# Shield_Amir_Shalev_V_0_1.net
KiCad netlist of a schematic drawn in EasyEDA
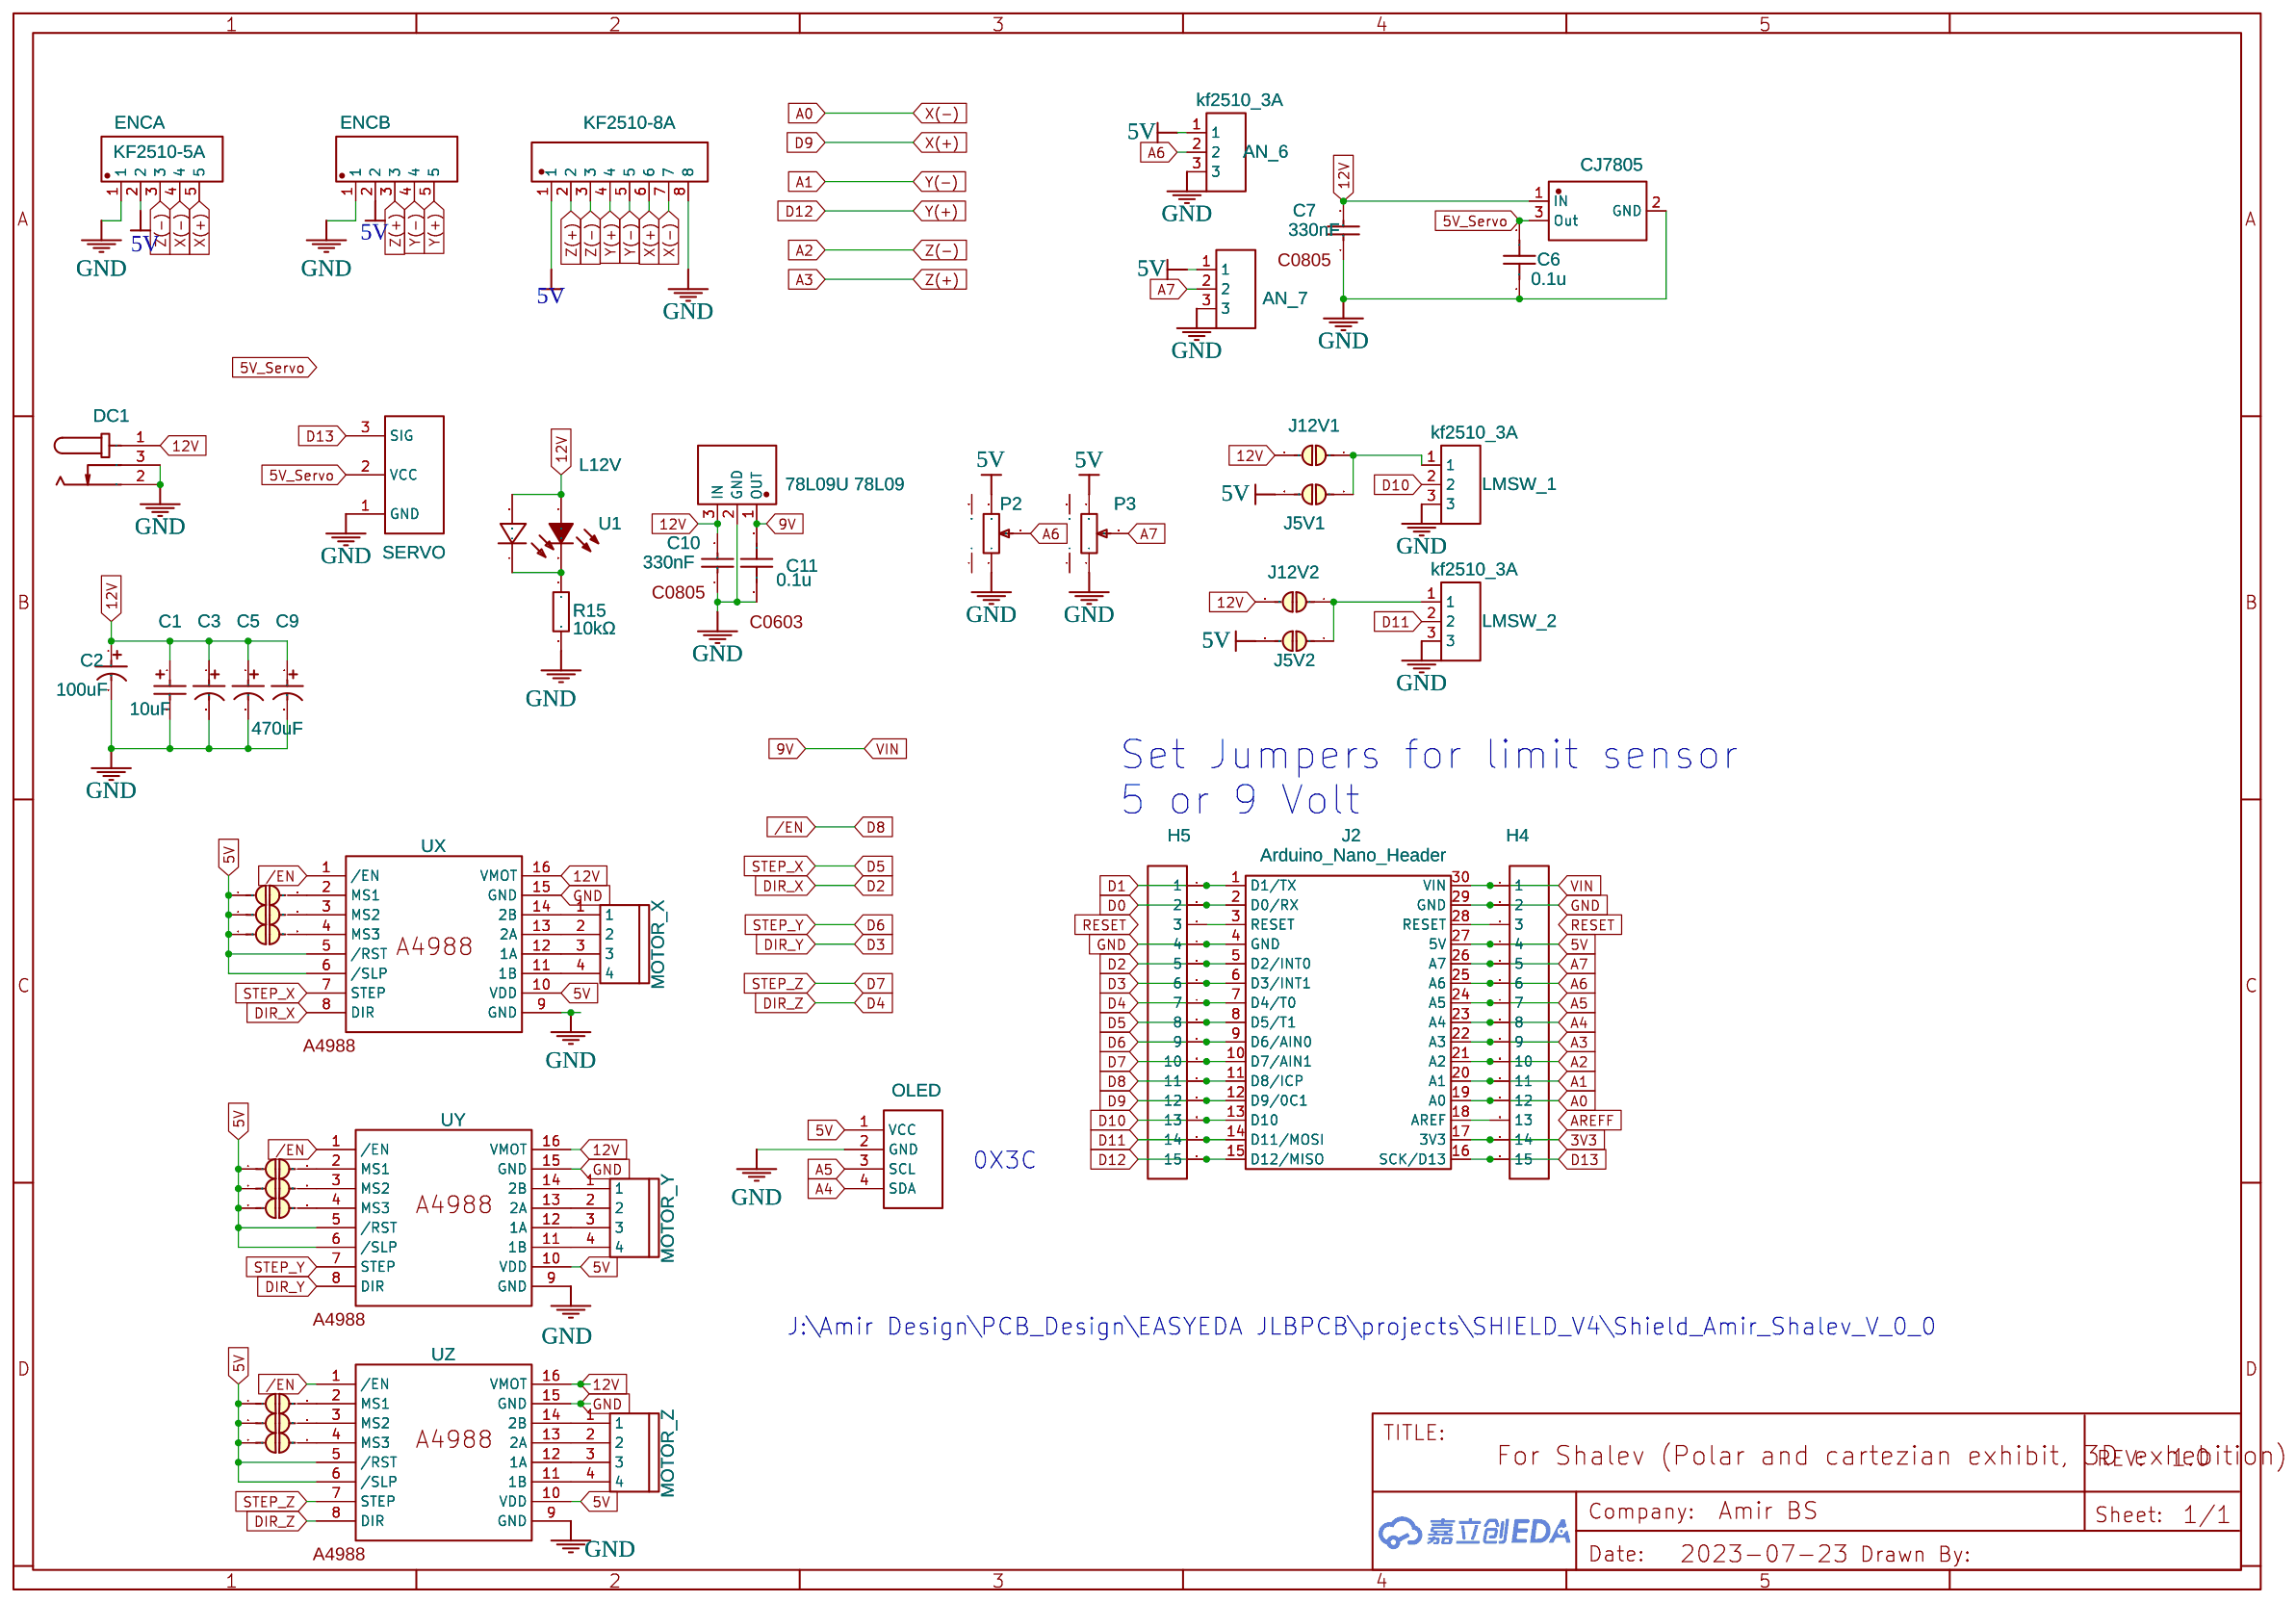
[diagram p0: schematic sheet]

(export (version "E")
  (design (tool "Eeschema 10.0.6"))
  (components
    (comp (ref "AN_6")
      (value "kf2510_3A")
      (fields (field (name "Manufacturer Part") "2510-3A") (field (name "Manufacturer") "BOOMELE(博穆精密)"))
      (libsource (lib "") (part "kf2510_3A_1"))
    )
    (comp (ref "AN_7")
      (value "kf2510_3A")
      (fields (field (name "Manufacturer Part") "2510-3A") (field (name "Manufacturer") "BOOMELE(博穆精密)"))
      (libsource (lib "") (part "kf2510_3A_1"))
    )
    (comp (ref "C1")
      (value "10uF")
      (fields (field (name "Manufacturer Part") "TAJA106K016RNJ") (field (name "Manufacturer") "Kyocera AVX"))
      (libsource (lib "") (part "TAJA106K016RNJ"))
    )
    (comp (ref "C2")
      (value "100uF")
      (fields
        (field (name "Manufacturer Part") "KM107M035E11RR0VH2FP0")
        (field (name "Manufacturer") "CX(承兴)")
      )
      (libsource (lib "") (part "100uF 35V 6.3*11"))
    )
    (comp (ref "C3")
      (value "470uF")
      (fields
        (field (name "Manufacturer Part") "GR477M025F12RR0VH4FP0")
        (field (name "Manufacturer") "CX(承兴)")
      )
      (libsource (lib "") (part "470uF 25V 8*12Black high frequency"))
    )
    (comp (ref "C5")
      (value "470uF")
      (fields
        (field (name "Manufacturer Part") "GR477M025F12RR0VH4FP0")
        (field (name "Manufacturer") "CX(承兴)")
      )
      (libsource (lib "") (part "470uF 25V 8*12Black high frequency"))
    )
    (comp (ref "C6") (value "0.1u") (libsource (lib "") (part "C_0603_US_1")))
    (comp (ref "C7")
      (value "330nF")
      (fields (field (name "Manufacturer Part") "0805B334K500NT") (field (name "Manufacturer") "FH(风华)"))
      (libsource (lib "") (part "0805B334K500NT"))
    )
    (comp (ref "C9")
      (value "470uF")
      (fields
        (field (name "Manufacturer Part") "GR477M025F12RR0VH4FP0")
        (field (name "Manufacturer") "CX(承兴)")
      )
      (libsource (lib "") (part "470uF 25V 8*12Black high frequency"))
    )
    (comp (ref "C10")
      (value "330nF")
      (fields (field (name "Manufacturer Part") "0805B334K500NT") (field (name "Manufacturer") "FH(风华)"))
      (libsource (lib "") (part "0805B334K500NT"))
    )
    (comp (ref "C11") (value "0.1u") (libsource (lib "") (part "C_0603_US")))
    (comp (ref "CN2")
      (value "KF2510-8A")
      (fields (field (name "Manufacturer Part") "2510-8A") (field (name "Manufacturer") "BOOMELE(博穆精密)"))
      (libsource (lib "") (part "KF2510-8A"))
    )
    (comp (ref "DC1")
      (value "DC")
      (fields
        (field (name "BOM_Manufacturer Part") "DC005-2.0MM")
        (field (name "BOM_Supplier Part") "C111567")
      )
      (libsource (lib "") (part "DC005-2.0MM"))
    )
    (comp (ref "ENCA")
      (value "KF2510-5A")
      (fields (field (name "Manufacturer Part") "2510-5A") (field (name "Manufacturer") "BOOMELE(博穆精密)"))
      (libsource (lib "") (part "KF2510-5A_1"))
    )
    (comp (ref "ENCB")
      (value "KF2510-5A")
      (fields (field (name "Manufacturer Part") "2510-5A") (field (name "Manufacturer") "BOOMELE(博穆精密)"))
      (libsource (lib "") (part "KF2510-5A"))
    )
    (comp (ref "H4")
      (value "HDR-F-2.54_1x15")
      (fields (field (name "BOM_Supplier Part") "C124408"))
      (libsource (lib "") (part "HDR-F-2.54_1x15"))
    )
    (comp (ref "H5")
      (value "HDR-F-2.54_1x15")
      (fields (field (name "BOM_Supplier Part") "C124408"))
      (libsource (lib "") (part "HDR-F-2.54_1x15_1"))
    )
    (comp (ref "J2") (value "Arduino_Nano_Header") (libsource (lib "") (part "Arduino_Nano_Header")))
    (comp (ref "J5V1") (value "JUMPER-SMT_2") (libsource (lib "") (part "JUMPER-SMT_2_3")))
    (comp (ref "J5V2") (value "JUMPER-SMT_2") (libsource (lib "") (part "JUMPER-SMT_2_3")))
    (comp (ref "J12V1") (value "JUMPER-SMT_2") (libsource (lib "") (part "JUMPER-SMT_2_4")))
    (comp (ref "J12V2") (value "JUMPER-SMT_2") (libsource (lib "") (part "JUMPER-SMT_2_4")))
    (comp (ref "JX1") (value "JUMPER-SMT_2") (libsource (lib "") (part "JUMPER-SMT_2_1")))
    (comp (ref "JX2") (value "JUMPER-SMT_2") (libsource (lib "") (part "JUMPER-SMT_2_1")))
    (comp (ref "JX3") (value "JUMPER-SMT_2") (libsource (lib "") (part "JUMPER-SMT_2_1")))
    (comp (ref "JY1") (value "JUMPER-SMT_2") (libsource (lib "") (part "JUMPER-SMT_2_2")))
    (comp (ref "JY2") (value "JUMPER-SMT_2") (libsource (lib "") (part "JUMPER-SMT_2_2")))
    (comp (ref "JY3") (value "JUMPER-SMT_2") (libsource (lib "") (part "JUMPER-SMT_2_2")))
    (comp (ref "JZ1") (value "JUMPER-SMT_2") (libsource (lib "") (part "JUMPER-SMT_2")))
    (comp (ref "JZ2") (value "JUMPER-SMT_2") (libsource (lib "") (part "JUMPER-SMT_2")))
    (comp (ref "JZ3") (value "JUMPER-SMT_2") (libsource (lib "") (part "JUMPER-SMT_2")))
    (comp (ref "L12V")
      (value "LED")
      (fields
        (field (name "BOM_Manufacturer Part") "19-217/BHC-ZL1M2RY/3T")
        (field (name "BOM_Supplier Part") "C72041")
      )
      (libsource (lib "") (part "19-217/BHC-ZL1M2RY/3T"))
    )
    (comp (ref "LMSW_1")
      (value "kf2510_3A")
      (fields (field (name "Manufacturer Part") "2510-3A") (field (name "Manufacturer") "BOOMELE(博穆精密)"))
      (libsource (lib "") (part "kf2510_3A"))
    )
    (comp (ref "LMSW_2")
      (value "kf2510_3A")
      (fields (field (name "Manufacturer Part") "2510-3A") (field (name "Manufacturer") "BOOMELE(博穆精密)"))
      (libsource (lib "") (part "kf2510_3A"))
    )
    (comp (ref "MOTOR_X")
      (value "XH2.54-4AW")
      (fields (field (name "Manufacturer Part") "XH-4AW") (field (name "Manufacturer") "BOOMELE(博穆精密)"))
      (libsource (lib "") (part "XH2.54-4AW_1"))
    )
    (comp (ref "MOTOR_Y")
      (value "XH2.54-4AW")
      (fields (field (name "Manufacturer Part") "XH-4AW") (field (name "Manufacturer") "BOOMELE(博穆精密)"))
      (libsource (lib "") (part "XH2.54-4AW"))
    )
    (comp (ref "MOTOR_Z")
      (value "XH2.54-4AW")
      (fields (field (name "Manufacturer Part") "XH-4AW") (field (name "Manufacturer") "BOOMELE(博穆精密)"))
      (libsource (lib "") (part "XH2.54-4AW_2"))
    )
    (comp (ref "OLED")
      (value "1.3 inch OLED SSH1106 I2C 128x64 copy")
      (libsource (lib "") (part "1.3 inch OLED SSH1106 I2C 128x64 copy"))
    )
    (comp (ref "P2")
      (value "长柄旋转电位器")
      (fields (field (name "BOM_Supplier Part") "C2874842"))
      (libsource (lib "") (part "长柄旋转电位器"))
    )
    (comp (ref "P3")
      (value "长柄旋转电位器")
      (fields (field (name "BOM_Supplier Part") "C2874842"))
      (libsource (lib "") (part "长柄旋转电位器"))
    )
    (comp (ref "R15")
      (value "10kΩ")
      (fields
        (field (name "BOM_Manufacturer Part") "0603WAF1002T5E")
        (field (name "BOM_Supplier Part") "C25804")
      )
      (libsource (lib "") (part "0603WAF1002T5E"))
    )
    (comp (ref "SERVO")
      (value "Servo+3d")
      (fields (field (name "BOM_Manufacturer Part") "New SchematicLib"))
      (libsource (lib "") (part "Servo+3d"))
    )
    (comp (ref "U1")
      (value "LED-DIP-3MM_RED")
      (fields (field (name "Manufacturer Part") "LED-DIP-3MM_Red"))
      (libsource (lib "") (part "LED-DIP-3MM_RED"))
    )
    (comp (ref "U2")
      (value "CJ7805")
      (fields (field (name "Manufacturer Part") "CJ7805 3%") (field (name "Manufacturer") "CJ(江苏长电/长晶)"))
      (libsource (lib "") (part "CJ7805 3%"))
    )
    (comp (ref "U5")
      (value "78L09U 78L09")
      (fields (field (name "Manufacturer") "CBI(创基)"))
      (libsource (lib "") (part "78L09U 78L09"))
    )
    (comp (ref "UX") (value "A4988") (libsource (lib "") (part "A4988_2")))
    (comp (ref "UY") (value "A4988") (libsource (lib "") (part "A4988_1")))
    (comp (ref "UZ") (value "A4988") (libsource (lib "") (part "A4988")))
  )
  (nets
    (net (code "1") (name "3V3") (class "Default")
      (node (ref "H4") (pin "14") (pinfunction "14_14") (pintype "unspecified"))
      (node (ref "J2") (pin "17") (pinfunction "3V3_17") (pintype "unspecified"))
    )
    (net (code "2") (name "5V") (class "Default")
      (node (ref "AN_6") (pin "1") (pinfunction "1_1") (pintype "unspecified"))
      (node (ref "AN_7") (pin "1") (pinfunction "1_1") (pintype "unspecified"))
      (node (ref "CN2") (pin "1") (pinfunction "1_1") (pintype "unspecified"))
      (node (ref "ENCA") (pin "2") (pinfunction "2_2") (pintype "unspecified"))
      (node (ref "ENCB") (pin "2") (pinfunction "2_2") (pintype "unspecified"))
      (node (ref "H4") (pin "4") (pinfunction "4_4") (pintype "unspecified"))
      (node (ref "J2") (pin "27") (pinfunction "5V_27") (pintype "unspecified"))
      (node (ref "J5V1") (pin "2") (pinfunction "2_2") (pintype "bidirectional"))
      (node (ref "J5V2") (pin "2") (pinfunction "2_2") (pintype "bidirectional"))
      (node (ref "JX1") (pin "1") (pinfunction "1_1") (pintype "bidirectional"))
      (node (ref "JX2") (pin "1") (pinfunction "1_1") (pintype "bidirectional"))
      (node (ref "JX3") (pin "1") (pinfunction "1_1") (pintype "bidirectional"))
      (node (ref "JY1") (pin "1") (pinfunction "1_1") (pintype "bidirectional"))
      (node (ref "JY2") (pin "1") (pinfunction "1_1") (pintype "bidirectional"))
      (node (ref "JY3") (pin "1") (pinfunction "1_1") (pintype "bidirectional"))
      (node (ref "JZ1") (pin "1") (pinfunction "1_1") (pintype "bidirectional"))
      (node (ref "JZ2") (pin "1") (pinfunction "1_1") (pintype "bidirectional"))
      (node (ref "JZ3") (pin "1") (pinfunction "1_1") (pintype "bidirectional"))
      (node (ref "OLED") (pin "1") (pinfunction "VCC_1") (pintype "passive"))
      (node (ref "P2") (pin "3") (pinfunction "3_3") (pintype "input"))
      (node (ref "P3") (pin "3") (pinfunction "3_3") (pintype "input"))
      (node (ref "UX") (pin "10") (pinfunction "VDD_10") (pintype "unspecified"))
      (node (ref "UX") (pin "5") (pinfunction "/RST_5") (pintype "unspecified"))
      (node (ref "UX") (pin "6") (pinfunction "/SLP_6") (pintype "unspecified"))
      (node (ref "UY") (pin "10") (pinfunction "VDD_10") (pintype "unspecified"))
      (node (ref "UY") (pin "5") (pinfunction "/RST_5") (pintype "unspecified"))
      (node (ref "UY") (pin "6") (pinfunction "/SLP_6") (pintype "unspecified"))
      (node (ref "UZ") (pin "10") (pinfunction "VDD_10") (pintype "unspecified"))
      (node (ref "UZ") (pin "5") (pinfunction "/RST_5") (pintype "unspecified"))
      (node (ref "UZ") (pin "6") (pinfunction "/SLP_6") (pintype "unspecified"))
    )
    (net (code "3") (name "5V_Servo") (class "Default")
      (node (ref "C6") (pin "2") (pinfunction "2_2") (pintype "unspecified"))
      (node (ref "SERVO") (pin "2") (pinfunction "VCC_2") (pintype "unspecified"))
      (node (ref "U2") (pin "3") (pinfunction "Out_3") (pintype "unspecified"))
    )
    (net (code "4") (name "9V") (class "Default")
      (node (ref "C11") (pin "2") (pinfunction "2_2") (pintype "unspecified"))
      (node (ref "H4") (pin "1") (pinfunction "1_1") (pintype "unspecified"))
      (node (ref "J2") (pin "30") (pinfunction "VIN_30") (pintype "unspecified"))
      (node (ref "U5") (pin "1") (pinfunction "OUT_1") (pintype "unspecified"))
    )
    (net (code "5") (name "12V") (class "Default")
      (node (ref "C1") (pin "1") (pinfunction "1_1") (pintype "input"))
      (node (ref "C10") (pin "2") (pinfunction "2_2") (pintype "input"))
      (node (ref "C2") (pin "1") (pinfunction "1_1") (pintype "input"))
      (node (ref "C3") (pin "1") (pinfunction "1_1") (pintype "input"))
      (node (ref "C5") (pin "1") (pinfunction "1_1") (pintype "input"))
      (node (ref "C7") (pin "2") (pinfunction "2_2") (pintype "input"))
      (node (ref "C9") (pin "1") (pinfunction "1_1") (pintype "input"))
      (node (ref "DC1") (pin "1") (pinfunction "1_1") (pintype "unspecified"))
      (node (ref "J12V1") (pin "2") (pinfunction "2_2") (pintype "bidirectional"))
      (node (ref "J12V2") (pin "2") (pinfunction "2_2") (pintype "bidirectional"))
      (node (ref "L12V") (pin "1") (pinfunction "A_1") (pintype "input"))
      (node (ref "U1") (pin "2") (pinfunction "2_2") (pintype "unspecified"))
      (node (ref "U2") (pin "1") (pinfunction "IN_1") (pintype "unspecified"))
      (node (ref "U5") (pin "3") (pinfunction "IN_3") (pintype "unspecified"))
      (node (ref "UX") (pin "16") (pinfunction "VMOT_16") (pintype "unspecified"))
      (node (ref "UY") (pin "16") (pinfunction "VMOT_16") (pintype "unspecified"))
      (node (ref "UZ") (pin "16") (pinfunction "VMOT_16") (pintype "unspecified"))
    )
    (net (code "6") (name "A0") (class "Default")
      (node (ref "CN2") (pin "7") (pinfunction "7_7") (pintype "unspecified"))
      (node (ref "ENCA") (pin "4") (pinfunction "4_4") (pintype "unspecified"))
      (node (ref "H4") (pin "12") (pinfunction "12_12") (pintype "unspecified"))
      (node (ref "J2") (pin "19") (pinfunction "A0_19") (pintype "unspecified"))
    )
    (net (code "7") (name "A1") (class "Default")
      (node (ref "CN2") (pin "5") (pinfunction "5_5") (pintype "unspecified"))
      (node (ref "ENCB") (pin "4") (pinfunction "4_4") (pintype "unspecified"))
      (node (ref "H4") (pin "11") (pinfunction "11_11") (pintype "unspecified"))
      (node (ref "J2") (pin "20") (pinfunction "A1_20") (pintype "unspecified"))
    )
    (net (code "8") (name "A2") (class "Default")
      (node (ref "CN2") (pin "3") (pinfunction "3_3") (pintype "unspecified"))
      (node (ref "ENCA") (pin "3") (pinfunction "3_3") (pintype "unspecified"))
      (node (ref "H4") (pin "10") (pinfunction "10_10") (pintype "unspecified"))
      (node (ref "J2") (pin "21") (pinfunction "A2_21") (pintype "unspecified"))
    )
    (net (code "9") (name "A3") (class "Default")
      (node (ref "CN2") (pin "2") (pinfunction "2_2") (pintype "unspecified"))
      (node (ref "ENCB") (pin "3") (pinfunction "3_3") (pintype "unspecified"))
      (node (ref "H4") (pin "9") (pinfunction "9_9") (pintype "unspecified"))
      (node (ref "J2") (pin "22") (pinfunction "A3_22") (pintype "unspecified"))
    )
    (net (code "10") (name "A4") (class "Default")
      (node (ref "H4") (pin "8") (pinfunction "8_8") (pintype "unspecified"))
      (node (ref "J2") (pin "23") (pinfunction "A4_23") (pintype "unspecified"))
      (node (ref "OLED") (pin "4") (pinfunction "SDA_4") (pintype "bidirectional"))
    )
    (net (code "11") (name "A5") (class "Default")
      (node (ref "H4") (pin "7") (pinfunction "7_7") (pintype "unspecified"))
      (node (ref "J2") (pin "24") (pinfunction "A5_24") (pintype "unspecified"))
      (node (ref "OLED") (pin "3") (pinfunction "SCL_3") (pintype "bidirectional"))
    )
    (net (code "12") (name "A6") (class "Default")
      (node (ref "AN_6") (pin "2") (pinfunction "2_2") (pintype "unspecified"))
      (node (ref "H4") (pin "6") (pinfunction "6_6") (pintype "unspecified"))
      (node (ref "J2") (pin "25") (pinfunction "A6_25") (pintype "unspecified"))
      (node (ref "P2") (pin "2") (pinfunction "2_2") (pintype "input"))
    )
    (net (code "13") (name "A7") (class "Default")
      (node (ref "AN_7") (pin "2") (pinfunction "2_2") (pintype "unspecified"))
      (node (ref "H4") (pin "5") (pinfunction "5_5") (pintype "unspecified"))
      (node (ref "J2") (pin "26") (pinfunction "A7_26") (pintype "unspecified"))
      (node (ref "P3") (pin "2") (pinfunction "2_2") (pintype "input"))
    )
    (net (code "15") (name "D0") (class "Default")
      (node (ref "H5") (pin "2") (pinfunction "2_2") (pintype "unspecified"))
      (node (ref "J2") (pin "2") (pinfunction "D0/RX_2") (pintype "unspecified"))
    )
    (net (code "16") (name "D1") (class "Default")
      (node (ref "H5") (pin "1") (pinfunction "1_1") (pintype "unspecified"))
      (node (ref "J2") (pin "1") (pinfunction "D1/TX_1") (pintype "unspecified"))
    )
    (net (code "17") (name "D2") (class "Default")
      (node (ref "H5") (pin "5") (pinfunction "5_5") (pintype "unspecified"))
      (node (ref "J2") (pin "5") (pinfunction "D2/INT0_5") (pintype "unspecified"))
      (node (ref "UX") (pin "8") (pinfunction "DIR_8") (pintype "unspecified"))
    )
    (net (code "18") (name "D3") (class "Default")
      (node (ref "H5") (pin "6") (pinfunction "6_6") (pintype "unspecified"))
      (node (ref "J2") (pin "6") (pinfunction "D3/INT1_6") (pintype "unspecified"))
      (node (ref "UY") (pin "8") (pinfunction "DIR_8") (pintype "unspecified"))
    )
    (net (code "19") (name "D4") (class "Default")
      (node (ref "H5") (pin "7") (pinfunction "7_7") (pintype "unspecified"))
      (node (ref "J2") (pin "7") (pinfunction "D4/T0_7") (pintype "unspecified"))
      (node (ref "UZ") (pin "8") (pinfunction "DIR_8") (pintype "unspecified"))
    )
    (net (code "20") (name "D5") (class "Default")
      (node (ref "H5") (pin "8") (pinfunction "8_8") (pintype "unspecified"))
      (node (ref "J2") (pin "8") (pinfunction "D5/T1_8") (pintype "unspecified"))
      (node (ref "UX") (pin "7") (pinfunction "STEP_7") (pintype "unspecified"))
    )
    (net (code "21") (name "D6") (class "Default")
      (node (ref "H5") (pin "9") (pinfunction "9_9") (pintype "unspecified"))
      (node (ref "J2") (pin "9") (pinfunction "D6/AIN0_9") (pintype "unspecified"))
      (node (ref "UY") (pin "7") (pinfunction "STEP_7") (pintype "unspecified"))
    )
    (net (code "22") (name "D7") (class "Default")
      (node (ref "H5") (pin "10") (pinfunction "10_10") (pintype "unspecified"))
      (node (ref "J2") (pin "10") (pinfunction "D7/AIN1_10") (pintype "unspecified"))
      (node (ref "UZ") (pin "7") (pinfunction "STEP_7") (pintype "unspecified"))
    )
    (net (code "23") (name "D8") (class "Default")
      (node (ref "H5") (pin "11") (pinfunction "11_11") (pintype "unspecified"))
      (node (ref "J2") (pin "11") (pinfunction "D8/ICP_11") (pintype "unspecified"))
      (node (ref "UX") (pin "1") (pinfunction "/EN_1") (pintype "unspecified"))
      (node (ref "UY") (pin "1") (pinfunction "/EN_1") (pintype "unspecified"))
      (node (ref "UZ") (pin "1") (pinfunction "/EN_1") (pintype "unspecified"))
    )
    (net (code "24") (name "D9") (class "Default")
      (node (ref "CN2") (pin "6") (pinfunction "6_6") (pintype "unspecified"))
      (node (ref "ENCA") (pin "5") (pinfunction "5_5") (pintype "unspecified"))
      (node (ref "H5") (pin "12") (pinfunction "12_12") (pintype "unspecified"))
      (node (ref "J2") (pin "12") (pinfunction "D9/0C1_12") (pintype "unspecified"))
    )
    (net (code "25") (name "D10") (class "Default")
      (node (ref "H5") (pin "13") (pinfunction "13_13") (pintype "unspecified"))
      (node (ref "J2") (pin "13") (pinfunction "D10_13") (pintype "unspecified"))
      (node (ref "LMSW_1") (pin "2") (pinfunction "2_2") (pintype "unspecified"))
    )
    (net (code "26") (name "D11") (class "Default")
      (node (ref "H5") (pin "14") (pinfunction "14_14") (pintype "unspecified"))
      (node (ref "J2") (pin "14") (pinfunction "D11/MOSI_14") (pintype "unspecified"))
      (node (ref "LMSW_2") (pin "2") (pinfunction "2_2") (pintype "unspecified"))
    )
    (net (code "27") (name "D12") (class "Default")
      (node (ref "CN2") (pin "4") (pinfunction "4_4") (pintype "unspecified"))
      (node (ref "ENCB") (pin "5") (pinfunction "5_5") (pintype "unspecified"))
      (node (ref "H5") (pin "15") (pinfunction "15_15") (pintype "unspecified"))
      (node (ref "J2") (pin "15") (pinfunction "D12/MISO_15") (pintype "unspecified"))
    )
    (net (code "28") (name "D13") (class "Default")
      (node (ref "H4") (pin "15") (pinfunction "15_15") (pintype "unspecified"))
      (node (ref "J2") (pin "16") (pinfunction "SCK/D13_16") (pintype "unspecified"))
      (node (ref "SERVO") (pin "3") (pinfunction "SIG_3") (pintype "unspecified"))
    )
    (net (code "29") (name "GND") (class "Default")
      (node (ref "AN_6") (pin "3") (pinfunction "3_3") (pintype "unspecified"))
      (node (ref "AN_7") (pin "3") (pinfunction "3_3") (pintype "unspecified"))
      (node (ref "C1") (pin "2") (pinfunction "2_2") (pintype "input"))
      (node (ref "C10") (pin "1") (pinfunction "1_1") (pintype "input"))
      (node (ref "C11") (pin "1") (pinfunction "1_1") (pintype "unspecified"))
      (node (ref "C2") (pin "2") (pinfunction "2_2") (pintype "input"))
      (node (ref "C3") (pin "2") (pinfunction "2_2") (pintype "input"))
      (node (ref "C5") (pin "2") (pinfunction "2_2") (pintype "input"))
      (node (ref "C6") (pin "1") (pinfunction "1_1") (pintype "unspecified"))
      (node (ref "C7") (pin "1") (pinfunction "1_1") (pintype "input"))
      (node (ref "C9") (pin "2") (pinfunction "2_2") (pintype "input"))
      (node (ref "CN2") (pin "8") (pinfunction "8_8") (pintype "unspecified"))
      (node (ref "DC1") (pin "2") (pinfunction "2_2") (pintype "unspecified"))
      (node (ref "DC1") (pin "3") (pinfunction "3_3") (pintype "unspecified"))
      (node (ref "ENCA") (pin "1") (pinfunction "1_1") (pintype "unspecified"))
      (node (ref "ENCB") (pin "1") (pinfunction "1_1") (pintype "unspecified"))
      (node (ref "H4") (pin "2") (pinfunction "2_2") (pintype "unspecified"))
      (node (ref "H5") (pin "4") (pinfunction "4_4") (pintype "unspecified"))
      (node (ref "J2") (pin "29") (pinfunction "GND_29") (pintype "unspecified"))
      (node (ref "J2") (pin "4") (pinfunction "GND_4") (pintype "unspecified"))
      (node (ref "LMSW_1") (pin "3") (pinfunction "3_3") (pintype "unspecified"))
      (node (ref "LMSW_2") (pin "3") (pinfunction "3_3") (pintype "unspecified"))
      (node (ref "OLED") (pin "2") (pinfunction "GND_2") (pintype "passive"))
      (node (ref "P2") (pin "1") (pinfunction "1_1") (pintype "input"))
      (node (ref "P3") (pin "1") (pinfunction "1_1") (pintype "input"))
      (node (ref "R15") (pin "2") (pinfunction "2_2") (pintype "input"))
      (node (ref "SERVO") (pin "1") (pinfunction "GND_1") (pintype "unspecified"))
      (node (ref "U2") (pin "2") (pinfunction "GND_2") (pintype "unspecified"))
      (node (ref "U5") (pin "2") (pinfunction "GND_2") (pintype "unspecified"))
      (node (ref "UX") (pin "15") (pinfunction "GND_15") (pintype "unspecified"))
      (node (ref "UX") (pin "9") (pinfunction "GND_9") (pintype "unspecified"))
      (node (ref "UY") (pin "15") (pinfunction "GND_15") (pintype "unspecified"))
      (node (ref "UY") (pin "9") (pinfunction "GND_9") (pintype "unspecified"))
      (node (ref "UZ") (pin "15") (pinfunction "GND_15") (pintype "unspecified"))
      (node (ref "UZ") (pin "9") (pinfunction "GND_9") (pintype "unspecified"))
    )
    (net (code "30") (name "Net-(H4-Pad3)") (class "Default")
      (node (ref "H4") (pin "3") (pinfunction "3_3") (pintype "unspecified"))
      (node (ref "J2") (pin "28") (pinfunction "RESET_28") (pintype "unspecified"))
    )
    (net (code "31") (name "Net-(H5-Pad3)") (class "Default")
      (node (ref "H5") (pin "3") (pinfunction "3_3") (pintype "unspecified"))
      (node (ref "J2") (pin "3") (pinfunction "RESET_3") (pintype "unspecified"))
    )
    (net (code "32") (name "Net-(J2-AREF)") (class "Default")
      (node (ref "H4") (pin "13") (pinfunction "13_13") (pintype "unspecified"))
      (node (ref "J2") (pin "18") (pinfunction "AREF_18") (pintype "unspecified"))
    )
    (net (code "33") (name "Net-(J12V1-Pad1)") (class "Default")
      (node (ref "J12V1") (pin "1") (pinfunction "1_1") (pintype "bidirectional"))
      (node (ref "J5V1") (pin "1") (pinfunction "1_1") (pintype "bidirectional"))
      (node (ref "LMSW_1") (pin "1") (pinfunction "1_1") (pintype "unspecified"))
    )
    (net (code "34") (name "Net-(J12V2-Pad1)") (class "Default")
      (node (ref "J12V2") (pin "1") (pinfunction "1_1") (pintype "bidirectional"))
      (node (ref "J5V2") (pin "1") (pinfunction "1_1") (pintype "bidirectional"))
      (node (ref "LMSW_2") (pin "1") (pinfunction "1_1") (pintype "unspecified"))
    )
    (net (code "35") (name "Net-(L12V-C)") (class "Default")
      (node (ref "L12V") (pin "2") (pinfunction "C_2") (pintype "input"))
      (node (ref "R15") (pin "1") (pinfunction "1_1") (pintype "input"))
      (node (ref "U1") (pin "1") (pinfunction "1_1") (pintype "unspecified"))
    )
    (net (code "36") (name "Net-(UX-1A)") (class "Default")
      (node (ref "MOTOR_X") (pin "3") (pinfunction "3_3") (pintype "unspecified"))
      (node (ref "UX") (pin "12") (pinfunction "1A_12") (pintype "unspecified"))
    )
    (net (code "37") (name "Net-(UX-1B)") (class "Default")
      (node (ref "MOTOR_X") (pin "4") (pinfunction "4_4") (pintype "unspecified"))
      (node (ref "UX") (pin "11") (pinfunction "1B_11") (pintype "unspecified"))
    )
    (net (code "38") (name "Net-(UX-2A)") (class "Default")
      (node (ref "MOTOR_X") (pin "2") (pinfunction "2_2") (pintype "unspecified"))
      (node (ref "UX") (pin "13") (pinfunction "2A_13") (pintype "unspecified"))
    )
    (net (code "39") (name "Net-(UX-2B)") (class "Default")
      (node (ref "MOTOR_X") (pin "1") (pinfunction "1_1") (pintype "unspecified"))
      (node (ref "UX") (pin "14") (pinfunction "2B_14") (pintype "unspecified"))
    )
    (net (code "40") (name "Net-(UX-MS1)") (class "Default")
      (node (ref "JX1") (pin "2") (pinfunction "2_2") (pintype "bidirectional"))
      (node (ref "UX") (pin "2") (pinfunction "MS1_2") (pintype "unspecified"))
    )
    (net (code "41") (name "Net-(UX-MS2)") (class "Default")
      (node (ref "JX2") (pin "2") (pinfunction "2_2") (pintype "bidirectional"))
      (node (ref "UX") (pin "3") (pinfunction "MS2_3") (pintype "unspecified"))
    )
    (net (code "42") (name "Net-(UX-MS3)") (class "Default")
      (node (ref "JX3") (pin "2") (pinfunction "2_2") (pintype "bidirectional"))
      (node (ref "UX") (pin "4") (pinfunction "MS3_4") (pintype "unspecified"))
    )
    (net (code "43") (name "Net-(UY-1A)") (class "Default")
      (node (ref "MOTOR_Y") (pin "3") (pinfunction "3_3") (pintype "unspecified"))
      (node (ref "UY") (pin "12") (pinfunction "1A_12") (pintype "unspecified"))
    )
    (net (code "44") (name "Net-(UY-1B)") (class "Default")
      (node (ref "MOTOR_Y") (pin "4") (pinfunction "4_4") (pintype "unspecified"))
      (node (ref "UY") (pin "11") (pinfunction "1B_11") (pintype "unspecified"))
    )
    (net (code "45") (name "Net-(UY-2A)") (class "Default")
      (node (ref "MOTOR_Y") (pin "2") (pinfunction "2_2") (pintype "unspecified"))
      (node (ref "UY") (pin "13") (pinfunction "2A_13") (pintype "unspecified"))
    )
    (net (code "46") (name "Net-(UY-2B)") (class "Default")
      (node (ref "MOTOR_Y") (pin "1") (pinfunction "1_1") (pintype "unspecified"))
      (node (ref "UY") (pin "14") (pinfunction "2B_14") (pintype "unspecified"))
    )
    (net (code "47") (name "Net-(UY-MS1)") (class "Default")
      (node (ref "JY1") (pin "2") (pinfunction "2_2") (pintype "bidirectional"))
      (node (ref "UY") (pin "2") (pinfunction "MS1_2") (pintype "unspecified"))
    )
    (net (code "48") (name "Net-(UY-MS2)") (class "Default")
      (node (ref "JY2") (pin "2") (pinfunction "2_2") (pintype "bidirectional"))
      (node (ref "UY") (pin "3") (pinfunction "MS2_3") (pintype "unspecified"))
    )
    (net (code "49") (name "Net-(UY-MS3)") (class "Default")
      (node (ref "JY3") (pin "2") (pinfunction "2_2") (pintype "bidirectional"))
      (node (ref "UY") (pin "4") (pinfunction "MS3_4") (pintype "unspecified"))
    )
    (net (code "50") (name "Net-(UZ-1A)") (class "Default")
      (node (ref "MOTOR_Z") (pin "3") (pinfunction "3_3") (pintype "unspecified"))
      (node (ref "UZ") (pin "12") (pinfunction "1A_12") (pintype "unspecified"))
    )
    (net (code "51") (name "Net-(UZ-1B)") (class "Default")
      (node (ref "MOTOR_Z") (pin "4") (pinfunction "4_4") (pintype "unspecified"))
      (node (ref "UZ") (pin "11") (pinfunction "1B_11") (pintype "unspecified"))
    )
    (net (code "52") (name "Net-(UZ-2A)") (class "Default")
      (node (ref "MOTOR_Z") (pin "2") (pinfunction "2_2") (pintype "unspecified"))
      (node (ref "UZ") (pin "13") (pinfunction "2A_13") (pintype "unspecified"))
    )
    (net (code "53") (name "Net-(UZ-2B)") (class "Default")
      (node (ref "MOTOR_Z") (pin "1") (pinfunction "1_1") (pintype "unspecified"))
      (node (ref "UZ") (pin "14") (pinfunction "2B_14") (pintype "unspecified"))
    )
    (net (code "54") (name "Net-(UZ-MS1)") (class "Default")
      (node (ref "JZ1") (pin "2") (pinfunction "2_2") (pintype "bidirectional"))
      (node (ref "UZ") (pin "2") (pinfunction "MS1_2") (pintype "unspecified"))
    )
    (net (code "55") (name "Net-(UZ-MS2)") (class "Default")
      (node (ref "JZ2") (pin "2") (pinfunction "2_2") (pintype "bidirectional"))
      (node (ref "UZ") (pin "3") (pinfunction "MS2_3") (pintype "unspecified"))
    )
    (net (code "56") (name "Net-(UZ-MS3)") (class "Default")
      (node (ref "JZ3") (pin "2") (pinfunction "2_2") (pintype "bidirectional"))
      (node (ref "UZ") (pin "4") (pinfunction "MS3_4") (pintype "unspecified"))
    )
    (net (code "58") (name "unconnected-(P2-Pad4)") (class "Default")
      (node (ref "P2") (pin "4") (pinfunction "4_4") (pintype "input"))
    )
    (net (code "59") (name "unconnected-(P2-Pad5)") (class "Default")
      (node (ref "P2") (pin "5") (pinfunction "5_5") (pintype "input"))
    )
    (net (code "60") (name "unconnected-(P3-Pad4)") (class "Default")
      (node (ref "P3") (pin "4") (pinfunction "4_4") (pintype "input"))
    )
    (net (code "61") (name "unconnected-(P3-Pad5)") (class "Default")
      (node (ref "P3") (pin "5") (pinfunction "5_5") (pintype "input"))
    )
  )
)
